# accelerometer.net
KiCad netlist of a schematic drawn in EAGLE
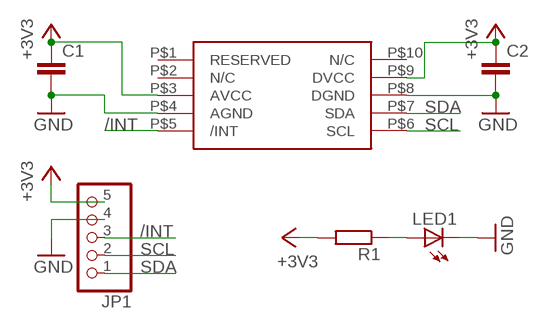
[diagram p0: schematic, sheet 1]

(export (version "E")
  (design (tool "Eeschema 10.0.6"))
  (components
    (comp (ref "C1")
      (value "C-EUC0805K")
      (footprint "eagle-import:C0805K")
      (libsource (lib "eagle-import") (part "C-EUC0805K"))
    )
    (comp (ref "C2")
      (value "C-EUC0805K")
      (footprint "eagle-import:C0805K")
      (libsource (lib "eagle-import") (part "C-EUC0805K"))
    )
    (comp (ref "JP1")
      (value "PINHD-1X5")
      (footprint "eagle-import:1X05")
      (libsource (lib "eagle-import") (part "PINHD-1X5"))
    )
    (comp (ref "LED1")
      (value "LED0805")
      (footprint "eagle-import:CHIP-LED0805")
      (libsource (lib "eagle-import") (part "LED0805"))
    )
    (comp (ref "R1")
      (value "R-EU_R0805")
      (footprint "eagle-import:R0805")
      (libsource (lib "eagle-import") (part "R-EU_R0805"))
    )
    (comp (ref "U$1")
      (value "MMA7660DFN-10-HAND")
      (footprint "eagle-import:DFN-10-HAND")
      (libsource (lib "eagle-import") (part "MMA7660DFN-10-HAND"))
    )
  )
  (nets
    (net (code "1") (name "+3V3") (class "Default")
      (node (ref "C1") (pin "1") (pinfunction "1_1") (pintype "passive"))
      (node (ref "C2") (pin "1") (pinfunction "1_1") (pintype "passive"))
      (node (ref "JP1") (pin "5") (pinfunction "5_5") (pintype "passive"))
      (node (ref "R1") (pin "2") (pinfunction "2_2") (pintype "passive"))
      (node (ref "U$1") (pin "P$3") (pinfunction "AVCC_P$3") (pintype "bidirectional"))
      (node (ref "U$1") (pin "P$9") (pinfunction "DVCC_P$9") (pintype "bidirectional"))
    )
    (net (code "2") (name "/SCL") (class "Default")
      (node (ref "JP1") (pin "2") (pinfunction "2_2") (pintype "passive"))
      (node (ref "U$1") (pin "P$6") (pinfunction "SCL_P$6") (pintype "bidirectional"))
    )
    (net (code "3") (name "/SDA") (class "Default")
      (node (ref "JP1") (pin "1") (pinfunction "1_1") (pintype "passive"))
      (node (ref "U$1") (pin "P$7") (pinfunction "SDA_P$7") (pintype "bidirectional"))
    )
    (net (code "4") (name "/{slash}INT") (class "Default")
      (node (ref "JP1") (pin "3") (pinfunction "3_3") (pintype "passive"))
      (node (ref "U$1") (pin "P$5") (pinfunction "/INT_P$5") (pintype "bidirectional"))
    )
    (net (code "5") (name "GND") (class "Default")
      (node (ref "C1") (pin "2") (pinfunction "2_2") (pintype "passive"))
      (node (ref "C2") (pin "2") (pinfunction "2_2") (pintype "passive"))
      (node (ref "JP1") (pin "4") (pinfunction "4_4") (pintype "passive"))
      (node (ref "LED1") (pin "C") (pinfunction "C_C") (pintype "passive"))
      (node (ref "U$1") (pin "P$4") (pinfunction "AGND_P$4") (pintype "bidirectional"))
      (node (ref "U$1") (pin "P$8") (pinfunction "DGND_P$8") (pintype "bidirectional"))
    )
    (net (code "6") (name "Net-(LED1-PadA)") (class "Default")
      (node (ref "LED1") (pin "A") (pinfunction "A_A") (pintype "passive"))
      (node (ref "R1") (pin "1") (pinfunction "1_1") (pintype "passive"))
    )
    (net (code "7") (name "unconnected-(U$1-N{slash}C-PadP$2)") (class "Default")
      (node (ref "U$1") (pin "P$2") (pinfunction "N/C_P$2") (pintype "no_connect"))
    )
    (net (code "8") (name "unconnected-(U$1-N{slash}C-PadP$10)") (class "Default")
      (node (ref "U$1") (pin "P$10") (pinfunction "N/C_P$10") (pintype "no_connect"))
    )
    (net (code "9") (name "unconnected-(U$1-RESERVED-PadP$1)") (class "Default")
      (node (ref "U$1") (pin "P$1") (pinfunction "RESERVED_P$1") (pintype "bidirectional"))
    )
  )
)
